# High_Voltage_H-Bridge.net
KiCad netlist of a schematic drawn in Altium Designer
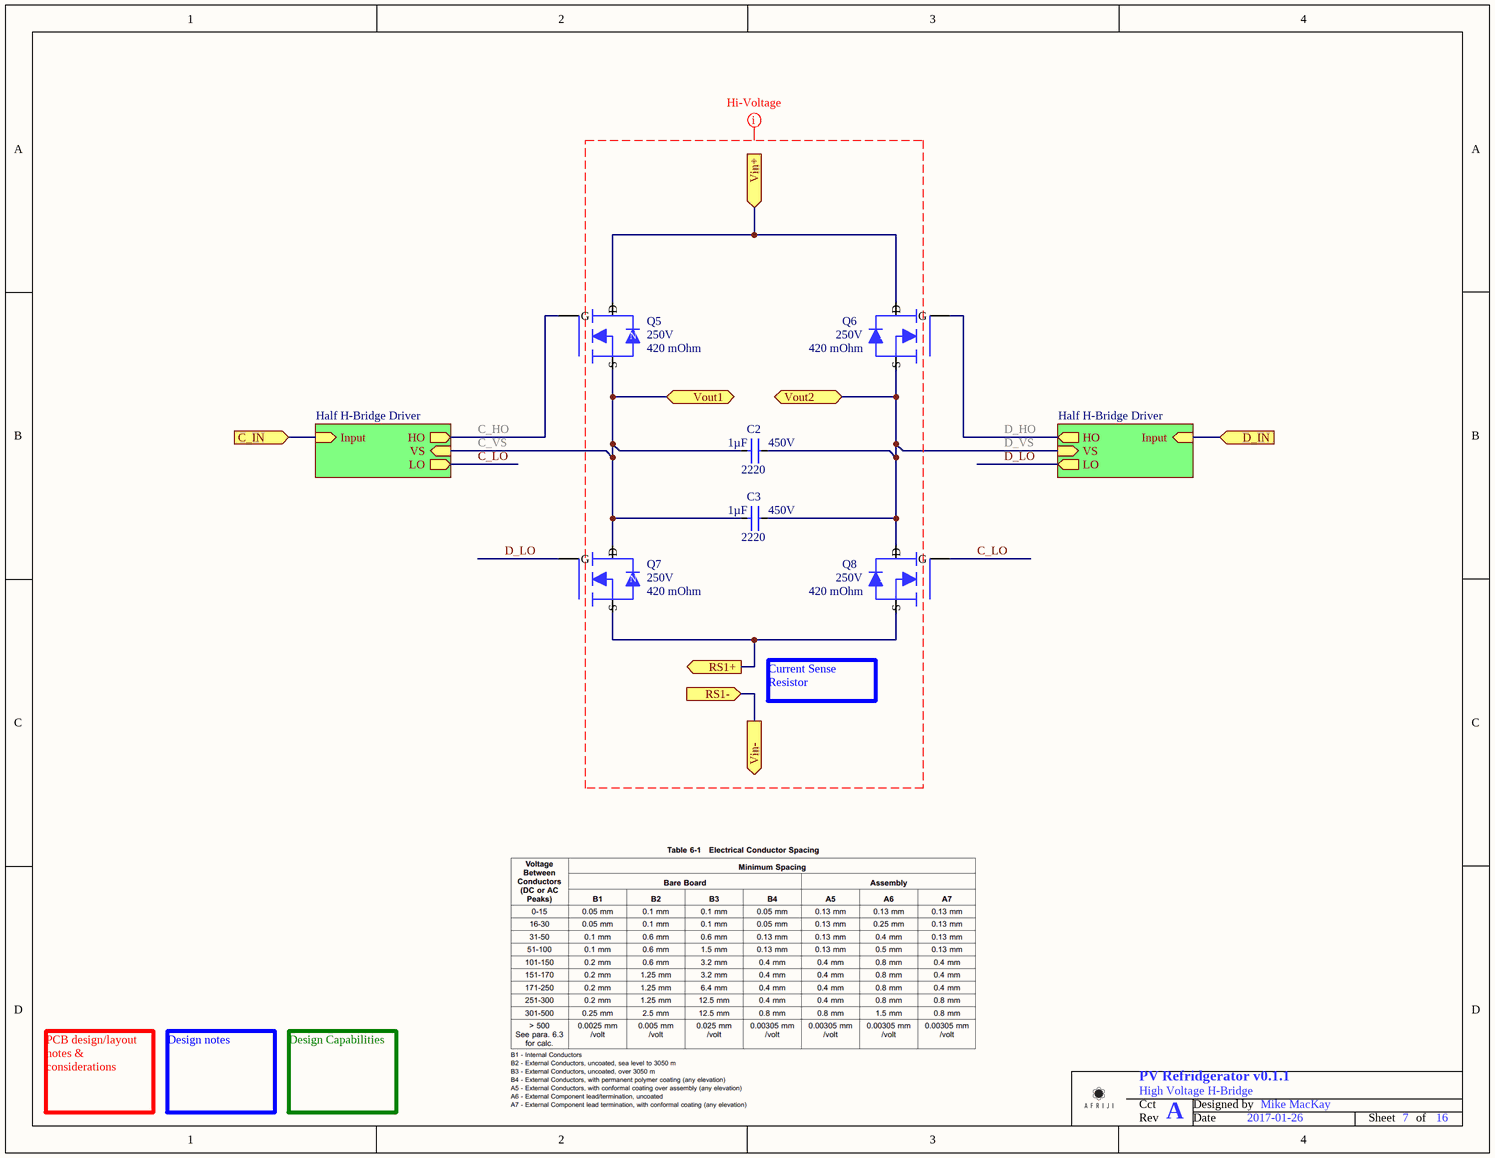
[diagram p0: High Voltage H-Bridge.SchDoc]

(export (version "E")
  (design (tool "Eeschema 10.0.6"))
  (components
    (comp (ref "C2")
      (value "1uF 2220 450V")
      (footprint "C2220 - Ceramic")
      (fields
        (field (name "MANUFACTURER") "TDK Corporation")
        (field (name "MANUFACTURER PART NUMBER") "CGA9P4X7T2W105M250KE")
        (field (name "TOLERANCE") "±20%")
        (field (name "CAPACITANCE") "1µF")
        (field (name "VOLTAGE - RATED") "450V")
        (field (name "PACKAGE / CASE") "2220")
      )
      (libsource (lib "Local Library") (part "1uF 2220 450V"))
    )
    (comp (ref "C3")
      (value "1uF 2220 450V")
      (footprint "C2220 - Ceramic")
      (fields
        (field (name "MANUFACTURER") "TDK Corporation")
        (field (name "MANUFACTURER PART NUMBER") "CGA9P4X7T2W105M250KE")
        (field (name "TOLERANCE") "±20%")
        (field (name "CAPACITANCE") "1µF")
        (field (name "VOLTAGE - RATED") "450V")
        (field (name "PACKAGE / CASE") "2220")
      )
      (libsource (lib "Local Library") (part "1uF 2220 450V"))
    )
    (comp (ref "Q5")
      (value "N-MOSFET - 66A/25V")
      (footprint "DPAK")
      (fields
        (field (name "MANUFACTURER") "Fairchild/ON Semiconductor")
        (field (name "MANUFACTURER PART NUMBER") "FQD9N25TM")
        (field (name "DRAIN TO SOURCE VOLTAGE (VDSS)") "250V")
        (field (name "RDS ON (MAX) @ ID, VGS") "420 mOhm")
      )
      (libsource (lib "Personal Library") (part "N-MOSFET - 66A/25V"))
    )
    (comp (ref "Q6")
      (value "N-MOSFET - 66A/25V")
      (footprint "DPAK")
      (fields
        (field (name "MANUFACTURER") "Fairchild/ON Semiconductor")
        (field (name "MANUFACTURER PART NUMBER") "FQD9N25TM")
        (field (name "DRAIN TO SOURCE VOLTAGE (VDSS)") "250V")
        (field (name "RDS ON (MAX) @ ID, VGS") "420 mOhm")
      )
      (libsource (lib "Personal Library") (part "N-MOSFET - 66A/25V"))
    )
    (comp (ref "Q7")
      (value "N-MOSFET - 66A/25V")
      (footprint "DPAK")
      (fields
        (field (name "MANUFACTURER") "Fairchild/ON Semiconductor")
        (field (name "MANUFACTURER PART NUMBER") "FQD9N25TM")
        (field (name "DRAIN TO SOURCE VOLTAGE (VDSS)") "250V")
        (field (name "RDS ON (MAX) @ ID, VGS") "420 mOhm")
      )
      (libsource (lib "Personal Library") (part "N-MOSFET - 66A/25V"))
    )
    (comp (ref "Q8")
      (value "N-MOSFET - 66A/25V")
      (footprint "DPAK")
      (fields
        (field (name "MANUFACTURER") "Fairchild/ON Semiconductor")
        (field (name "MANUFACTURER PART NUMBER") "FQD9N25TM")
        (field (name "DRAIN TO SOURCE VOLTAGE (VDSS)") "250V")
        (field (name "RDS ON (MAX) @ ID, VGS") "420 mOhm")
      )
      (libsource (lib "Personal Library") (part "N-MOSFET - 66A/25V"))
    )
  )
  (nets
    (net (code "1") (name "/C_HO") (class "Default")
      (node (ref "Q5") (pin "1") (pinfunction "G_1") (pintype "passive"))
    )
    (net (code "3") (name "/C_LO") (class "Default")
      (node (ref "Q8") (pin "1") (pinfunction "G_1") (pintype "passive"))
    )
    (net (code "4") (name "/C_VS") (class "Default")
      (node (ref "C2") (pin "1") (pinfunction "1_1") (pintype "passive"))
      (node (ref "C3") (pin "1") (pinfunction "1_1") (pintype "passive"))
      (node (ref "Q5") (pin "2") (pinfunction "S_2") (pintype "passive"))
      (node (ref "Q7") (pin "3") (pinfunction "D_3") (pintype "passive"))
    )
    (net (code "5") (name "/D_HO") (class "Default")
      (node (ref "Q6") (pin "1") (pinfunction "G_1") (pintype "passive"))
    )
    (net (code "7") (name "/D_LO") (class "Default")
      (node (ref "Q7") (pin "1") (pinfunction "G_1") (pintype "passive"))
    )
    (net (code "8") (name "/D_VS") (class "Default")
      (node (ref "C2") (pin "2") (pinfunction "2_2") (pintype "passive"))
      (node (ref "C3") (pin "2") (pinfunction "2_2") (pintype "passive"))
      (node (ref "Q6") (pin "2") (pinfunction "S_2") (pintype "passive"))
      (node (ref "Q8") (pin "3") (pinfunction "D_3") (pintype "passive"))
    )
    (net (code "9") (name "/RS1+") (class "Default")
      (node (ref "Q7") (pin "2") (pinfunction "S_2") (pintype "passive"))
      (node (ref "Q8") (pin "2") (pinfunction "S_2") (pintype "passive"))
    )
    (net (code "11") (name "/Vin+") (class "Default")
      (node (ref "Q5") (pin "3") (pinfunction "D_3") (pintype "passive"))
      (node (ref "Q6") (pin "3") (pinfunction "D_3") (pintype "passive"))
    )
  )
)
